# Breakout_schematic.net
KiCad netlist of a schematic drawn in Altium Designer
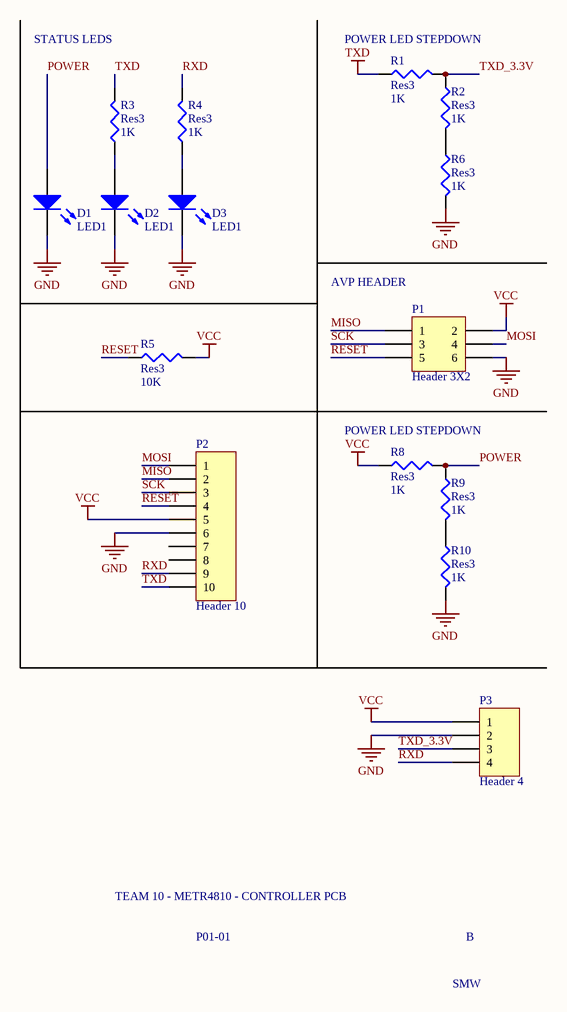
[diagram p0: Breakout_schematic.SchDoc]

(export (version "E")
  (design (tool "Eeschema 10.0.6"))
  (components
    (comp (ref "D1")
      (value "LED1")
      (footprint "L0603")
      (description "Typical RED GaAs LED")
      (fields (field (name "PUBLISHER") "Altium Limited"))
      (libsource (lib "Miscellaneous Devices") (part "LED1"))
    )
    (comp (ref "D2")
      (value "LED1")
      (footprint "L0603")
      (description "Typical RED GaAs LED")
      (fields (field (name "PUBLISHER") "Altium Limited"))
      (libsource (lib "Miscellaneous Devices") (part "LED1"))
    )
    (comp (ref "D3")
      (value "LED1")
      (footprint "L0603")
      (description "Typical RED GaAs LED")
      (fields (field (name "PUBLISHER") "Altium Limited"))
      (libsource (lib "Miscellaneous Devices") (part "LED1"))
    )
    (comp (ref "P1")
      (value "Header 3X2")
      (footprint "HDR2X3")
      (description "Header, 3-Pin, Dual row")
      (fields (field (name "PUBLISHER") "Altium Limited"))
      (libsource (lib "Miscellaneous Connectors") (part "Header 3X2"))
    )
    (comp (ref "P2")
      (value "Header 10")
      (footprint "HDR1X10")
      (description "Header, 10-Pin")
      (fields (field (name "PUBLISHER") "Altium Limited"))
      (libsource (lib "Miscellaneous Connectors") (part "Header 10"))
    )
    (comp (ref "P3")
      (value "Header 4")
      (footprint "HDR1X4")
      (description "Header, 4-Pin")
      (fields (field (name "PUBLISHER") "Altium Limited"))
      (libsource (lib "Miscellaneous Connectors") (part "Header 4"))
    )
    (comp (ref "R1")
      (value "Res3")
      (footprint "J1-0603")
      (description "Resistor")
      (fields (field (name "ALTIUM_VALUE") "1K") (field (name "PUBLISHER") "Altium Limited"))
      (libsource (lib "Miscellaneous Devices") (part "Res3"))
    )
    (comp (ref "R2")
      (value "Res3")
      (footprint "J1-0603")
      (description "Resistor")
      (fields (field (name "ALTIUM_VALUE") "1K") (field (name "PUBLISHER") "Altium Limited"))
      (libsource (lib "Miscellaneous Devices") (part "Res3"))
    )
    (comp (ref "R3")
      (value "Res3")
      (footprint "J1-0603")
      (description "Resistor")
      (fields (field (name "ALTIUM_VALUE") "1K") (field (name "PUBLISHER") "Altium Limited"))
      (libsource (lib "Miscellaneous Devices") (part "Res3"))
    )
    (comp (ref "R4")
      (value "Res3")
      (footprint "J1-0603")
      (description "Resistor")
      (fields (field (name "ALTIUM_VALUE") "1K") (field (name "PUBLISHER") "Altium Limited"))
      (libsource (lib "Miscellaneous Devices") (part "Res3"))
    )
    (comp (ref "R5")
      (value "Res3")
      (footprint "J1-0603")
      (description "Resistor")
      (fields (field (name "ALTIUM_VALUE") "10K") (field (name "PUBLISHER") "Altium Limited"))
      (libsource (lib "Miscellaneous Devices") (part "Res3"))
    )
    (comp (ref "R6")
      (value "Res3")
      (footprint "J1-0603")
      (description "Resistor")
      (fields (field (name "ALTIUM_VALUE") "1K") (field (name "PUBLISHER") "Altium Limited"))
      (libsource (lib "Miscellaneous Devices") (part "Res3"))
    )
    (comp (ref "R8")
      (value "Res3")
      (footprint "J1-0603")
      (description "Resistor")
      (fields (field (name "ALTIUM_VALUE") "1K") (field (name "PUBLISHER") "Altium Limited"))
      (libsource (lib "Miscellaneous Devices") (part "Res3"))
    )
    (comp (ref "R9")
      (value "Res3")
      (footprint "J1-0603")
      (description "Resistor")
      (fields (field (name "ALTIUM_VALUE") "1K") (field (name "PUBLISHER") "Altium Limited"))
      (libsource (lib "Miscellaneous Devices") (part "Res3"))
    )
    (comp (ref "R10")
      (value "Res3")
      (footprint "J1-0603")
      (description "Resistor")
      (fields (field (name "ALTIUM_VALUE") "1K") (field (name "PUBLISHER") "Altium Limited"))
      (libsource (lib "Miscellaneous Devices") (part "Res3"))
    )
  )
  (nets
    (net (code "1") (name "/MISO") (class "Default")
      (node (ref "P1") (pin "1") (pinfunction "1_1") (pintype "passive"))
      (node (ref "P2") (pin "2") (pinfunction "2_2") (pintype "passive"))
    )
    (net (code "2") (name "/MOSI") (class "Default")
      (node (ref "P1") (pin "4") (pinfunction "4_4") (pintype "passive"))
      (node (ref "P2") (pin "1") (pinfunction "1_1") (pintype "passive"))
    )
    (net (code "3") (name "/POWER") (class "Default")
      (node (ref "D1") (pin "1") (pinfunction "A_1") (pintype "passive"))
      (node (ref "R8") (pin "2") (pinfunction "2_2") (pintype "passive"))
      (node (ref "R9") (pin "1") (pinfunction "1_1") (pintype "passive"))
    )
    (net (code "4") (name "/RESET") (class "Default")
      (node (ref "P1") (pin "5") (pinfunction "5_5") (pintype "passive"))
      (node (ref "P2") (pin "4") (pinfunction "4_4") (pintype "passive"))
      (node (ref "R5") (pin "1") (pinfunction "1_1") (pintype "passive"))
    )
    (net (code "5") (name "/RXD") (class "Default")
      (node (ref "P2") (pin "9") (pinfunction "9_9") (pintype "passive"))
      (node (ref "P3") (pin "4") (pinfunction "4_4") (pintype "passive"))
      (node (ref "R4") (pin "2") (pinfunction "2_2") (pintype "passive"))
    )
    (net (code "6") (name "/SCK") (class "Default")
      (node (ref "P1") (pin "3") (pinfunction "3_3") (pintype "passive"))
      (node (ref "P2") (pin "3") (pinfunction "3_3") (pintype "passive"))
    )
    (net (code "7") (name "/TXD_3.3V") (class "Default")
      (node (ref "P3") (pin "3") (pinfunction "3_3") (pintype "passive"))
      (node (ref "R1") (pin "2") (pinfunction "2_2") (pintype "passive"))
      (node (ref "R2") (pin "1") (pinfunction "1_1") (pintype "passive"))
    )
    (net (code "8") (name "GND") (class "Default")
      (node (ref "D1") (pin "2") (pinfunction "K_2") (pintype "passive"))
      (node (ref "D2") (pin "2") (pinfunction "K_2") (pintype "passive"))
      (node (ref "D3") (pin "2") (pinfunction "K_2") (pintype "passive"))
      (node (ref "P1") (pin "6") (pinfunction "6_6") (pintype "passive"))
      (node (ref "P2") (pin "6") (pinfunction "6_6") (pintype "passive"))
      (node (ref "P3") (pin "2") (pinfunction "2_2") (pintype "passive"))
      (node (ref "R10") (pin "2") (pinfunction "2_2") (pintype "passive"))
      (node (ref "R6") (pin "2") (pinfunction "2_2") (pintype "passive"))
    )
    (net (code "9") (name "Net-(D2-A)") (class "Default")
      (node (ref "D2") (pin "1") (pinfunction "A_1") (pintype "passive"))
      (node (ref "R3") (pin "1") (pinfunction "1_1") (pintype "passive"))
    )
    (net (code "10") (name "Net-(D3-A)") (class "Default")
      (node (ref "D3") (pin "1") (pinfunction "A_1") (pintype "passive"))
      (node (ref "R4") (pin "1") (pinfunction "1_1") (pintype "passive"))
    )
    (net (code "11") (name "Net-(R2-Pad2)") (class "Default")
      (node (ref "R2") (pin "2") (pinfunction "2_2") (pintype "passive"))
      (node (ref "R6") (pin "1") (pinfunction "1_1") (pintype "passive"))
    )
    (net (code "12") (name "Net-(R10-Pad1)") (class "Default")
      (node (ref "R10") (pin "1") (pinfunction "1_1") (pintype "passive"))
      (node (ref "R9") (pin "2") (pinfunction "2_2") (pintype "passive"))
    )
    (net (code "13") (name "TXD") (class "Default")
      (node (ref "P2") (pin "10") (pinfunction "10_10") (pintype "passive"))
      (node (ref "R1") (pin "1") (pinfunction "1_1") (pintype "passive"))
      (node (ref "R3") (pin "2") (pinfunction "2_2") (pintype "passive"))
    )
    (net (code "14") (name "VCC") (class "Default")
      (node (ref "P1") (pin "2") (pinfunction "2_2") (pintype "passive"))
      (node (ref "P2") (pin "5") (pinfunction "5_5") (pintype "passive"))
      (node (ref "P3") (pin "1") (pinfunction "1_1") (pintype "passive"))
      (node (ref "R5") (pin "2") (pinfunction "2_2") (pintype "passive"))
      (node (ref "R8") (pin "1") (pinfunction "1_1") (pintype "passive"))
    )
    (net (code "15") (name "unconnected-(P2-Pad7)") (class "Default")
      (node (ref "P2") (pin "7") (pinfunction "7_7") (pintype "passive"))
    )
    (net (code "16") (name "unconnected-(P2-Pad8)") (class "Default")
      (node (ref "P2") (pin "8") (pinfunction "8_8") (pintype "passive"))
    )
  )
)
